# 3_3V_Buck_Converter.net
KiCad netlist of a schematic drawn in Altium Designer
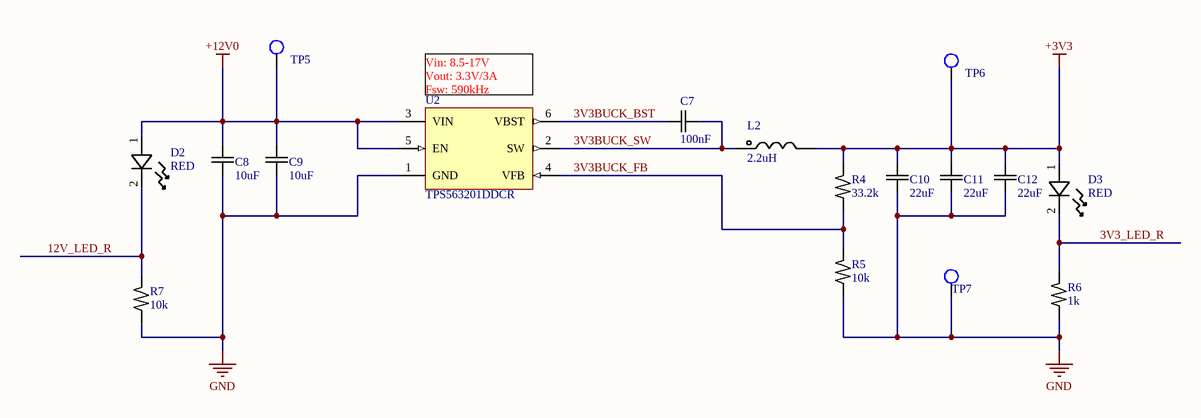
[diagram p0: 3.3V Buck Converter.SchDoc]

(export (version "E")
  (design (tool "Eeschema 10.0.6"))
  (components
    (comp (ref "C7")
      (value "100nF")
      (footprint "C0603")
      (description "CAP CER 100nF 50V X7R 0603")
      (fields (field (name "MF") "HRE") (field (name "MP") "CGA0603X7R104K500JT"))
      (libsource (lib "Components") (part "Cap_cer"))
    )
    (comp (ref "C8")
      (value "10uF")
      (footprint "C1206")
      (description "CAP CER 10uF 25V X7R 1206")
      (fields (field (name "MF") "SAMWHA") (field (name "MP") "CS3216X7R106K250NRI"))
      (libsource (lib "Components") (part "Cap_cer"))
    )
    (comp (ref "C9")
      (value "10uF")
      (footprint "C1206")
      (description "CAP CER 10uF 25V X7R 1206")
      (fields (field (name "MF") "SAMWHA") (field (name "MP") "CS3216X7R106K250NRI"))
      (libsource (lib "Components") (part "Cap_cer"))
    )
    (comp (ref "C10")
      (value "22uF")
      (footprint "C1206")
      (description "CAP CER 22uF 10V X7R 1206")
      (fields (field (name "MF") "CCTC") (field (name "MP") "TCC1206X7R226K100HT"))
      (libsource (lib "Components") (part "Cap_cer"))
    )
    (comp (ref "C11")
      (value "22uF")
      (footprint "C1206")
      (description "CAP CER 22uF 10V X7R 1206")
      (fields (field (name "MF") "CCTC") (field (name "MP") "TCC1206X7R226K100HT"))
      (libsource (lib "Components") (part "Cap_cer"))
    )
    (comp (ref "C12")
      (value "22uF")
      (footprint "C1206")
      (description "CAP CER 22uF 10V X7R 1206")
      (fields (field (name "MF") "CCTC") (field (name "MP") "TCC1206X7R226K100HT"))
      (libsource (lib "Components") (part "Cap_cer"))
    )
    (comp (ref "D2")
      (value "RED")
      (footprint "LED0805 RED")
      (description "LED RED WATER CLEAR 0805 SMD")
      (fields (field (name "MF") "XINGLIGHT") (field (name "MP") "XL-TD2012SURC"))
      (libsource (lib "Components") (part "LED"))
    )
    (comp (ref "D3")
      (value "RED")
      (footprint "LED0805 RED")
      (description "LED RED WATER CLEAR 0805 SMD")
      (fields (field (name "MF") "XINGLIGHT") (field (name "MP") "XL-TD2012SURC"))
      (libsource (lib "Components") (part "LED"))
    )
    (comp (ref "L2")
      (value "2.2uH")
      (footprint "Coil 7.2x6.6")
      (description "FIXED IND 2.2uH 9.5A 11.2mΩ SMD,7.2x6.6mm")
      (fields (field (name "MF") "SHOU HAN") (field (name "MP") "CYA0650-2.2UH"))
      (libsource (lib "Components") (part "Coil"))
    )
    (comp (ref "R4")
      (value "33.2k")
      (footprint "R0603")
      (description "RES 33.2kΩ ±1% 100mW 0603")
      (fields (field (name "MF") "FOJAN") (field (name "MP") "FRC0603F3322TS"))
      (libsource (lib "Components") (part "Res"))
    )
    (comp (ref "R5")
      (value "10k")
      (footprint "R0603")
      (description "RES 10kΩ ±1% 100mW 0603")
      (fields (field (name "MF") "FOJAN") (field (name "MP") "FRC0603F1002TS"))
      (libsource (lib "Components") (part "Res"))
    )
    (comp (ref "R6")
      (value "1k")
      (footprint "R0603")
      (description "RES 1kΩ ±5% 100mW 0603")
      (fields (field (name "MF") "VO") (field (name "MP") "SCR0603J1K"))
      (libsource (lib "Components") (part "Res"))
    )
    (comp (ref "R7")
      (value "10k")
      (footprint "R0603")
      (description "RES 10kΩ ±1% 100mW 0603")
      (fields (field (name "MF") "FOJAN") (field (name "MP") "FRC0603F1002TS"))
      (libsource (lib "Components") (part "Res"))
    )
    (comp (ref "TP5")
      (value "TestPoint")
      (footprint "TESTPOINT_SMD_1.27MM")
      (libsource (lib "Components") (part "TestPoint"))
    )
    (comp (ref "TP6")
      (value "TestPoint")
      (footprint "TESTPOINT_SMD_1.27MM")
      (libsource (lib "Components") (part "TestPoint"))
    )
    (comp (ref "TP7")
      (value "TestPoint")
      (footprint "TESTPOINT_SMD_1.27MM")
      (libsource (lib "Components") (part "TestPoint"))
    )
    (comp (ref "U2")
      (value "TPS563201DDCR")
      (footprint "SOT23-6")
      (fields (field (name "MF") "Texas Instruments"))
      (libsource (lib "Components") (part "TPS563201DDCR"))
    )
  )
  (nets
    (net (code "1") (name "+3V3") (class "Default")
      (node (ref "C10") (pin "1") (pinfunction "1_1") (pintype "passive"))
      (node (ref "C11") (pin "1") (pinfunction "1_1") (pintype "passive"))
      (node (ref "C12") (pin "1") (pinfunction "1_1") (pintype "passive"))
      (node (ref "D3") (pin "1") (pinfunction "1_1") (pintype "passive"))
      (node (ref "L2") (pin "2") (pinfunction "2_2") (pintype "passive"))
      (node (ref "R4") (pin "2") (pinfunction "2_2") (pintype "passive"))
      (node (ref "TP6") (pin "1") (pinfunction "1_1") (pintype "passive"))
    )
    (net (code "2") (name "+12V0") (class "Default")
      (node (ref "C8") (pin "2") (pinfunction "2_2") (pintype "passive"))
      (node (ref "C9") (pin "2") (pinfunction "2_2") (pintype "passive"))
      (node (ref "D2") (pin "1") (pinfunction "1_1") (pintype "passive"))
      (node (ref "TP5") (pin "1") (pinfunction "1_1") (pintype "passive"))
      (node (ref "U2") (pin "3") (pinfunction "VIN_3") (pintype "power_in"))
      (node (ref "U2") (pin "5") (pinfunction "EN_5") (pintype "input"))
    )
    (net (code "3") (name "/3V3BUCK_BST") (class "Default")
      (node (ref "C7") (pin "1") (pinfunction "1_1") (pintype "passive"))
      (node (ref "U2") (pin "6") (pinfunction "VBST_6") (pintype "output"))
    )
    (net (code "4") (name "/3V3BUCK_FB") (class "Default")
      (node (ref "R4") (pin "1") (pinfunction "1_1") (pintype "passive"))
      (node (ref "R5") (pin "2") (pinfunction "2_2") (pintype "passive"))
      (node (ref "U2") (pin "4") (pinfunction "VFB_4") (pintype "input"))
    )
    (net (code "5") (name "/3V3BUCK_SW") (class "Default")
      (node (ref "C7") (pin "2") (pinfunction "2_2") (pintype "passive"))
      (node (ref "L2") (pin "1") (pinfunction "1_1") (pintype "passive"))
      (node (ref "U2") (pin "2") (pinfunction "SW_2") (pintype "output"))
    )
    (net (code "6") (name "/3V3_LED_R") (class "Default")
      (node (ref "D3") (pin "2") (pinfunction "2_2") (pintype "passive"))
      (node (ref "R6") (pin "2") (pinfunction "2_2") (pintype "passive"))
    )
    (net (code "7") (name "/12V_LED_R") (class "Default")
      (node (ref "D2") (pin "2") (pinfunction "2_2") (pintype "passive"))
      (node (ref "R7") (pin "2") (pinfunction "2_2") (pintype "passive"))
    )
    (net (code "8") (name "GND") (class "Default")
      (node (ref "C10") (pin "2") (pinfunction "2_2") (pintype "passive"))
      (node (ref "C11") (pin "2") (pinfunction "2_2") (pintype "passive"))
      (node (ref "C12") (pin "2") (pinfunction "2_2") (pintype "passive"))
      (node (ref "C8") (pin "1") (pinfunction "1_1") (pintype "passive"))
      (node (ref "C9") (pin "1") (pinfunction "1_1") (pintype "passive"))
      (node (ref "R5") (pin "1") (pinfunction "1_1") (pintype "passive"))
      (node (ref "R6") (pin "1") (pinfunction "1_1") (pintype "passive"))
      (node (ref "R7") (pin "1") (pinfunction "1_1") (pintype "passive"))
      (node (ref "TP7") (pin "1") (pinfunction "1_1") (pintype "passive"))
      (node (ref "U2") (pin "1") (pinfunction "GND_1") (pintype "power_in"))
    )
  )
)
